# driver.net
KiCad netlist of a schematic drawn in EAGLE
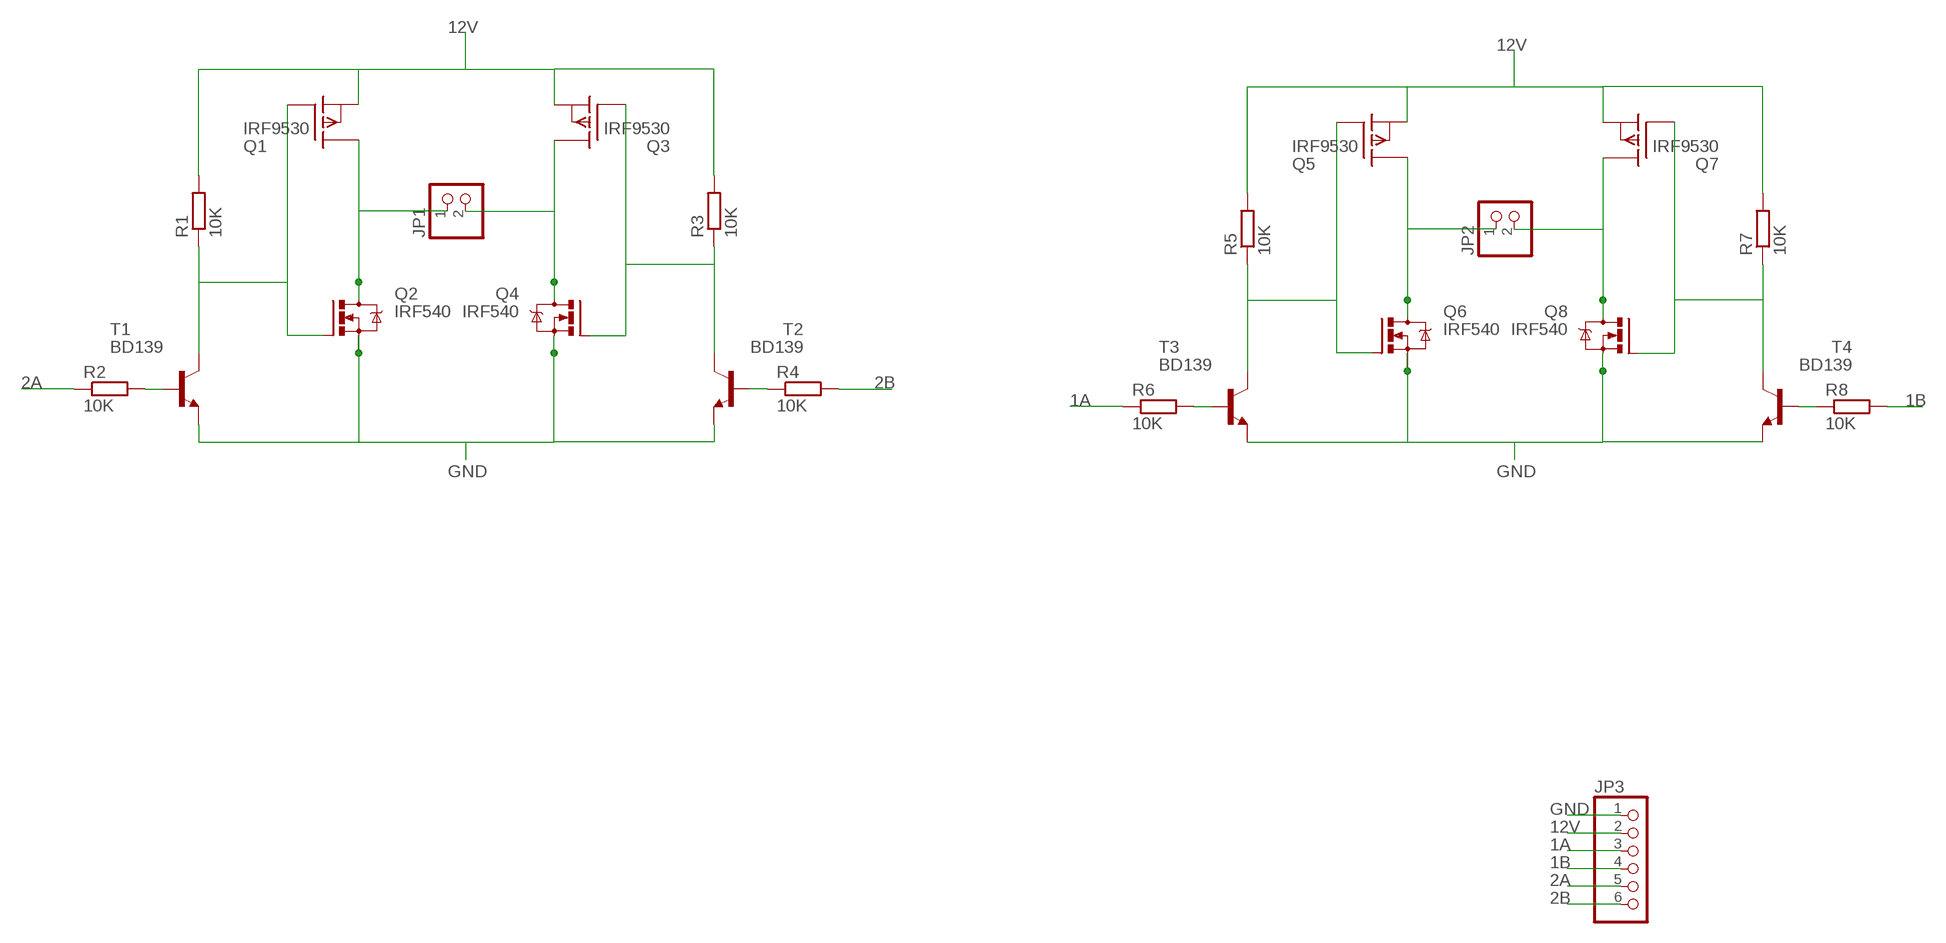
[diagram p0: schematic, sheet 1]

(export (version "E")
  (design (tool "Eeschema 10.0.6"))
  (components
    (comp (ref "JP1")
      (value "PINHD-1X2")
      (footprint "eagle-import:1X02")
      (libsource (lib "eagle-import") (part "PINHD-1X2"))
    )
    (comp (ref "JP2")
      (value "PINHD-1X2")
      (footprint "eagle-import:1X02")
      (libsource (lib "eagle-import") (part "PINHD-1X2"))
    )
    (comp (ref "JP3")
      (value "PINHD-1X6")
      (footprint "eagle-import:1X06")
      (libsource (lib "eagle-import") (part "PINHD-1X6"))
    )
    (comp (ref "Q1")
      (value "IRF9530")
      (footprint "eagle-import:TO220")
      (libsource (lib "eagle-import") (part "IRF9530"))
    )
    (comp (ref "Q2")
      (value "IRF540")
      (footprint "eagle-import:TO220BV")
      (libsource (lib "eagle-import") (part "IRF540"))
    )
    (comp (ref "Q3")
      (value "IRF9530")
      (footprint "eagle-import:TO220")
      (libsource (lib "eagle-import") (part "IRF9530"))
    )
    (comp (ref "Q4")
      (value "IRF540")
      (footprint "eagle-import:TO220BV")
      (libsource (lib "eagle-import") (part "IRF540"))
    )
    (comp (ref "Q5")
      (value "IRF9530")
      (footprint "eagle-import:TO220")
      (libsource (lib "eagle-import") (part "IRF9530"))
    )
    (comp (ref "Q6")
      (value "IRF540")
      (footprint "eagle-import:TO220BV")
      (libsource (lib "eagle-import") (part "IRF540"))
    )
    (comp (ref "Q7")
      (value "IRF9530")
      (footprint "eagle-import:TO220")
      (libsource (lib "eagle-import") (part "IRF9530"))
    )
    (comp (ref "Q8")
      (value "IRF540")
      (footprint "eagle-import:TO220BV")
      (libsource (lib "eagle-import") (part "IRF540"))
    )
    (comp (ref "R1")
      (value "10K")
      (footprint "eagle-import:0207_7")
      (libsource (lib "eagle-import") (part "R-EU_0207/7"))
    )
    (comp (ref "R2")
      (value "10K")
      (footprint "eagle-import:0207_7")
      (libsource (lib "eagle-import") (part "R-EU_0207/7"))
    )
    (comp (ref "R3")
      (value "10K")
      (footprint "eagle-import:0207_7")
      (libsource (lib "eagle-import") (part "R-EU_0207/7"))
    )
    (comp (ref "R4")
      (value "10K")
      (footprint "eagle-import:0207_7")
      (libsource (lib "eagle-import") (part "R-EU_0207/7"))
    )
    (comp (ref "R5")
      (value "10K")
      (footprint "eagle-import:0207_7")
      (libsource (lib "eagle-import") (part "R-EU_0207/7"))
    )
    (comp (ref "R6")
      (value "10K")
      (footprint "eagle-import:0207_7")
      (libsource (lib "eagle-import") (part "R-EU_0207/7"))
    )
    (comp (ref "R7")
      (value "10K")
      (footprint "eagle-import:0207_7")
      (libsource (lib "eagle-import") (part "R-EU_0207/7"))
    )
    (comp (ref "R8")
      (value "10K")
      (footprint "eagle-import:0207_7")
      (libsource (lib "eagle-import") (part "R-EU_0207/7"))
    )
    (comp (ref "T1")
      (value "BD139")
      (footprint "eagle-import:TO126")
      (libsource (lib "eagle-import") (part "BD139"))
    )
    (comp (ref "T2")
      (value "BD139")
      (footprint "eagle-import:TO126")
      (libsource (lib "eagle-import") (part "BD139"))
    )
    (comp (ref "T3")
      (value "BD139")
      (footprint "eagle-import:TO126")
      (libsource (lib "eagle-import") (part "BD139"))
    )
    (comp (ref "T4")
      (value "BD139")
      (footprint "eagle-import:TO126")
      (libsource (lib "eagle-import") (part "BD139"))
    )
  )
  (nets
    (net (code "1") (name "/1A") (class "Default")
      (node (ref "JP3") (pin "3") (pinfunction "3_3") (pintype "passive"))
      (node (ref "R6") (pin "1") (pinfunction "1_1") (pintype "passive"))
    )
    (net (code "2") (name "/1B") (class "Default")
      (node (ref "JP3") (pin "4") (pinfunction "4_4") (pintype "passive"))
      (node (ref "R8") (pin "2") (pinfunction "2_2") (pintype "passive"))
    )
    (net (code "3") (name "/2A") (class "Default")
      (node (ref "JP3") (pin "5") (pinfunction "5_5") (pintype "passive"))
      (node (ref "R2") (pin "1") (pinfunction "1_1") (pintype "passive"))
    )
    (net (code "4") (name "/2B") (class "Default")
      (node (ref "JP3") (pin "6") (pinfunction "6_6") (pintype "passive"))
      (node (ref "R4") (pin "2") (pinfunction "2_2") (pintype "passive"))
    )
    (net (code "5") (name "/12V") (class "Default")
      (node (ref "JP3") (pin "2") (pinfunction "2_2") (pintype "passive"))
      (node (ref "Q1") (pin "3") (pinfunction "S_3") (pintype "passive"))
      (node (ref "Q3") (pin "3") (pinfunction "S_3") (pintype "passive"))
      (node (ref "Q5") (pin "3") (pinfunction "S_3") (pintype "passive"))
      (node (ref "Q7") (pin "3") (pinfunction "S_3") (pintype "passive"))
      (node (ref "R1") (pin "2") (pinfunction "2_2") (pintype "passive"))
      (node (ref "R3") (pin "2") (pinfunction "2_2") (pintype "passive"))
      (node (ref "R5") (pin "2") (pinfunction "2_2") (pintype "passive"))
      (node (ref "R7") (pin "2") (pinfunction "2_2") (pintype "passive"))
    )
    (net (code "6") (name "/GND") (class "Default")
      (node (ref "JP3") (pin "1") (pinfunction "1_1") (pintype "passive"))
      (node (ref "Q2") (pin "S") (pinfunction "S_S") (pintype "passive"))
      (node (ref "Q4") (pin "S") (pinfunction "S_S") (pintype "passive"))
      (node (ref "Q6") (pin "S") (pinfunction "S_S") (pintype "passive"))
      (node (ref "Q8") (pin "S") (pinfunction "S_S") (pintype "passive"))
      (node (ref "T1") (pin "1") (pinfunction "E_1") (pintype "passive"))
      (node (ref "T2") (pin "1") (pinfunction "E_1") (pintype "passive"))
      (node (ref "T3") (pin "1") (pinfunction "E_1") (pintype "passive"))
      (node (ref "T4") (pin "1") (pinfunction "E_1") (pintype "passive"))
    )
    (net (code "7") (name "Net-(Q1-D)") (class "Default")
      (node (ref "JP1") (pin "1") (pinfunction "1_1") (pintype "passive"))
      (node (ref "Q1") (pin "2") (pinfunction "D_2") (pintype "passive"))
      (node (ref "Q2") (pin "D") (pinfunction "D_D") (pintype "passive"))
    )
    (net (code "8") (name "Net-(Q1-G)") (class "Default")
      (node (ref "Q1") (pin "1") (pinfunction "G_1") (pintype "passive"))
      (node (ref "Q2") (pin "G") (pinfunction "G_G") (pintype "passive"))
      (node (ref "R1") (pin "1") (pinfunction "1_1") (pintype "passive"))
      (node (ref "T1") (pin "2") (pinfunction "C_2") (pintype "passive"))
    )
    (net (code "9") (name "Net-(Q3-D)") (class "Default")
      (node (ref "JP1") (pin "2") (pinfunction "2_2") (pintype "passive"))
      (node (ref "Q3") (pin "2") (pinfunction "D_2") (pintype "passive"))
      (node (ref "Q4") (pin "D") (pinfunction "D_D") (pintype "passive"))
    )
    (net (code "10") (name "Net-(Q3-G)") (class "Default")
      (node (ref "Q3") (pin "1") (pinfunction "G_1") (pintype "passive"))
      (node (ref "Q4") (pin "G") (pinfunction "G_G") (pintype "passive"))
      (node (ref "R3") (pin "1") (pinfunction "1_1") (pintype "passive"))
      (node (ref "T2") (pin "2") (pinfunction "C_2") (pintype "passive"))
    )
    (net (code "11") (name "Net-(Q5-D)") (class "Default")
      (node (ref "JP2") (pin "1") (pinfunction "1_1") (pintype "passive"))
      (node (ref "Q5") (pin "2") (pinfunction "D_2") (pintype "passive"))
      (node (ref "Q6") (pin "D") (pinfunction "D_D") (pintype "passive"))
    )
    (net (code "12") (name "Net-(Q5-G)") (class "Default")
      (node (ref "Q5") (pin "1") (pinfunction "G_1") (pintype "passive"))
      (node (ref "Q6") (pin "G") (pinfunction "G_G") (pintype "passive"))
      (node (ref "R5") (pin "1") (pinfunction "1_1") (pintype "passive"))
      (node (ref "T3") (pin "2") (pinfunction "C_2") (pintype "passive"))
    )
    (net (code "13") (name "Net-(Q7-D)") (class "Default")
      (node (ref "JP2") (pin "2") (pinfunction "2_2") (pintype "passive"))
      (node (ref "Q7") (pin "2") (pinfunction "D_2") (pintype "passive"))
      (node (ref "Q8") (pin "D") (pinfunction "D_D") (pintype "passive"))
    )
    (net (code "14") (name "Net-(Q7-G)") (class "Default")
      (node (ref "Q7") (pin "1") (pinfunction "G_1") (pintype "passive"))
      (node (ref "Q8") (pin "G") (pinfunction "G_G") (pintype "passive"))
      (node (ref "R7") (pin "1") (pinfunction "1_1") (pintype "passive"))
      (node (ref "T4") (pin "2") (pinfunction "C_2") (pintype "passive"))
    )
    (net (code "15") (name "Net-(T1-B)") (class "Default")
      (node (ref "R2") (pin "2") (pinfunction "2_2") (pintype "passive"))
      (node (ref "T1") (pin "3") (pinfunction "B_3") (pintype "passive"))
    )
    (net (code "16") (name "Net-(T2-B)") (class "Default")
      (node (ref "R4") (pin "1") (pinfunction "1_1") (pintype "passive"))
      (node (ref "T2") (pin "3") (pinfunction "B_3") (pintype "passive"))
    )
    (net (code "17") (name "Net-(T3-B)") (class "Default")
      (node (ref "R6") (pin "2") (pinfunction "2_2") (pintype "passive"))
      (node (ref "T3") (pin "3") (pinfunction "B_3") (pintype "passive"))
    )
    (net (code "18") (name "Net-(T4-B)") (class "Default")
      (node (ref "R8") (pin "1") (pinfunction "1_1") (pintype "passive"))
      (node (ref "T4") (pin "3") (pinfunction "B_3") (pintype "passive"))
    )
  )
)
